# MCU.net
KiCad netlist of a schematic drawn in Altium Designer
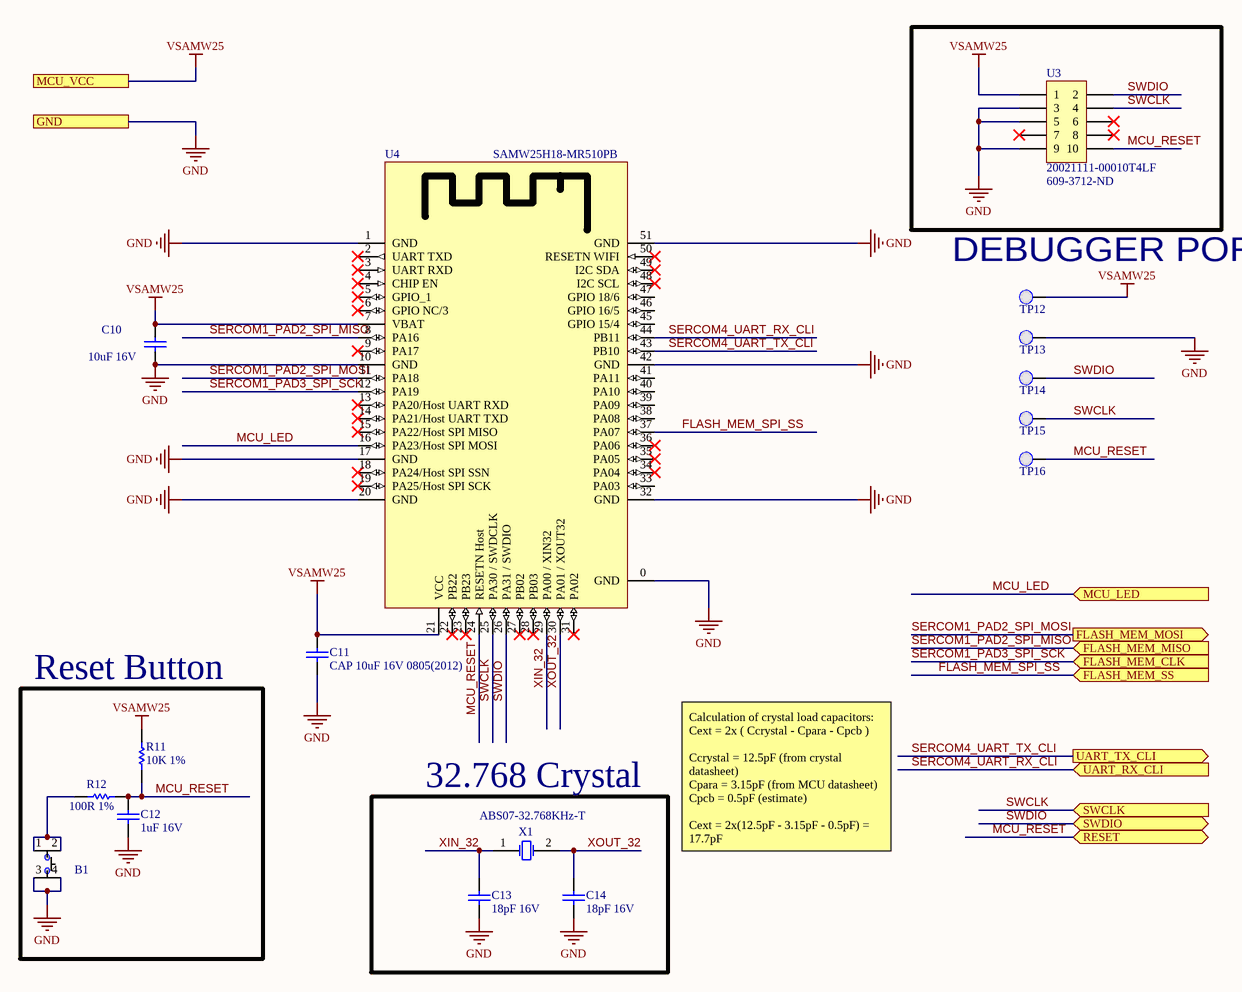
[diagram p0: MCU.SchDoc]

(export (version "E")
  (design (tool "Eeschema 10.0.6"))
  (components
    (comp (ref "B1")
      (value "PTS810 SJK 250 SMTR LFS")
      (footprint "PTS810 SJK 250 SMTR LFS")
      (description "SWITCH TACTILE SPST-NO 0.05A 16V Tactile Switch SPST-NO Top Actuated Surface Mount")
      (fields
        (field (name "MANUFACTURER") "ITT /  C&K Components")
        (field (name "MANUFACTURER PART NUMBER") "PTS810SJK250SMTRLFS")
      )
      (libsource (lib "Schematics") (part "PTS810 SJK 250 SMTR LFS"))
    )
    (comp (ref "C10")
      (value "10uF 16V")
      (footprint "CAPC0805(2012)145_N")
      (description "CAP 10uF 16V ±10% 0805 (2012 Metric) Thickness 1.45mm SMD")
      (fields (field (name "TOLERANCE") "Â±10%"))
      (libsource (lib "Altium Content Vault") (part "CAP"))
    )
    (comp (ref "C11")
      (value "CAP 10uF 16V 0805(2012)")
      (footprint "CAPC0805(2012)145_N")
      (description "CAP 10uF 16V ±10% 0805 (2012 Metric) Thickness 1.45mm SMD")
      (fields (field (name "TOLERANCE") "Â±10%"))
      (libsource (lib "Altium Content Vault") (part "CAP"))
    )
    (comp (ref "C12")
      (value "1uF 16V")
      (footprint "CAPC0603(1608)100_N")
      (description "CAP 1uF 16V ±5% 0603 (1608 Metric) Thickness 1mm SMD")
      (fields (field (name "TOLERANCE") "Â±5%"))
      (libsource (lib "Altium Content Vault") (part "CAP"))
    )
    (comp (ref "C13")
      (value "18pF 16V")
      (footprint "CAPC0603(1608)100_N")
      (description "CAP 18pF 16V ±5% 0603 (1608 Metric) Thickness 1mm SMD")
      (fields (field (name "TOLERANCE") "Â±5%"))
      (libsource (lib "Altium Content Vault") (part "CAP"))
    )
    (comp (ref "C14")
      (value "18pF 16V")
      (footprint "CAPC0603(1608)100_N")
      (description "CAP 18pF 16V ±5% 0603 (1608 Metric) Thickness 1mm SMD")
      (fields (field (name "TOLERANCE") "Â±5%"))
      (libsource (lib "Altium Content Vault") (part "CAP"))
    )
    (comp (ref "R11")
      (value "10K 1%")
      (footprint "RESC0603(1608)_N")
      (description "10K 0.1W 1% 0603 (1608 Metric)  SMD")
      (fields (field (name "POWER") "0.1 W") (field (name "TOLERANCE") "1 %"))
      (libsource (lib "Altium Content Vault") (part "RES"))
    )
    (comp (ref "R12")
      (value "100R 1%")
      (footprint "RESC0603(1608)_N")
      (description "100R 0.1W 1% 0603 (1608 Metric)  SMD")
      (fields (field (name "TOLERANCE") "1 %") (field (name "POWER") "0.1 W"))
      (libsource (lib "Altium Content Vault") (part "RES"))
    )
    (comp (ref "TP12")
      (value "0.1\" Pad")
      (footprint "PCBComponent")
      (libsource (lib "Components - 12.02.20 - 18.05") (part "0.1{dblquote} Pad-A.4"))
    )
    (comp (ref "TP13")
      (value "0.1\" Pad")
      (footprint "PCBComponent")
      (libsource (lib "Components - 12.02.20 - 18.05") (part "0.1{dblquote} Pad-A.4"))
    )
    (comp (ref "TP14")
      (value "0.1\" Pad")
      (footprint "PCBComponent")
      (libsource (lib "Components - 12.02.20 - 18.05") (part "0.1{dblquote} Pad-A.4"))
    )
    (comp (ref "TP15")
      (value "0.1\" Pad")
      (footprint "PCBComponent")
      (libsource (lib "Components - 12.02.20 - 18.05") (part "0.1{dblquote} Pad-A.4"))
    )
    (comp (ref "TP16")
      (value "0.1\" Pad")
      (footprint "PCBComponent")
      (libsource (lib "Components - 12.02.20 - 18.05") (part "0.1{dblquote} Pad-A.4"))
    )
    (comp (ref "U3")
      (value "20021111-00010T4LF")
      (footprint "20021111-00010T4LF")
      (description "CONN HEADER 10POS UNSHD VERT T/H")
      (fields
        (field (name "MANUFACTURER") "Amphenol / FCI")
        (field (name "SUPPLIER PART NUMBER 1") "609-3712-ND")
      )
      (libsource (lib "Schematics") (part "20021111-00010T4LF"))
    )
    (comp (ref "U4")
      (value "SAMW25H18-MR510PB")
      (footprint "SAMW25H18-MR510PB")
      (description "RF TXRX MODULE WIFI TRACE ANT")
      (fields
        (field (name "MANUFACTURER") "Atmel")
        (field (name "MANUFACTURER PART NUMBER") "ATSAMW25H18-MR510PB")
      )
      (libsource (lib "Schematics") (part "SAMW25H18-MR510PB"))
    )
    (comp (ref "X1")
      (value "ABS07-32.768KHz-T")
      (footprint "ABRA-ABS07-2_V")
      (description "Crystal, 32.768 kHz, 12.5 pF, -40 to 85 degC, SMD Low Profile 3.2 x 1.5 x 0.9 mm, Tape and Reel")
      (fields (field (name "MANUFACTURER") "Abracon"))
      (libsource (lib "Altium Content Vault") (part "ABRA-ABS07-2"))
    )
  )
  (nets
    (net (code "1") (name "/FLASH_MEM_SPI_SS") (class "Default")
      (node (ref "U4") (pin "37") (pinfunction "PA07_37") (pintype "bidirectional"))
    )
    (net (code "2") (name "/MCU_LED") (class "Default")
      (node (ref "U4") (pin "16") (pinfunction "PA23/Host_SPI_MOSI_16") (pintype "bidirectional"))
    )
    (net (code "3") (name "/MCU_RESET") (class "Default")
      (node (ref "C12") (pin "2") (pinfunction "2_2") (pintype "passive"))
      (node (ref "R11") (pin "1") (pinfunction "1_1") (pintype "passive"))
      (node (ref "R12") (pin "2") (pinfunction "2_2") (pintype "passive"))
      (node (ref "TP16") (pin "1") (pinfunction "PAD_1") (pintype "passive"))
      (node (ref "U3") (pin "10") (pinfunction "10_10") (pintype "passive"))
      (node (ref "U4") (pin "24") (pinfunction "RESETN_Host_24") (pintype "input"))
    )
    (net (code "4") (name "/SERCOM1_PAD2_SPI_MISO") (class "Default")
      (node (ref "U4") (pin "8") (pinfunction "PA16_8") (pintype "bidirectional"))
    )
    (net (code "5") (name "/SERCOM1_PAD2_SPI_MOSI") (class "Default")
      (node (ref "U4") (pin "11") (pinfunction "PA18_11") (pintype "bidirectional"))
    )
    (net (code "6") (name "/SERCOM1_PAD3_SPI_SCK") (class "Default")
      (node (ref "U4") (pin "12") (pinfunction "PA19_12") (pintype "bidirectional"))
    )
    (net (code "7") (name "/SERCOM4_UART_RX_CLI") (class "Default")
      (node (ref "U4") (pin "44") (pinfunction "PB11_44") (pintype "bidirectional"))
    )
    (net (code "8") (name "/SERCOM4_UART_TX_CLI") (class "Default")
      (node (ref "U4") (pin "43") (pinfunction "PB10_43") (pintype "bidirectional"))
    )
    (net (code "9") (name "/SWCLK") (class "Default")
      (node (ref "TP15") (pin "1") (pinfunction "PAD_1") (pintype "passive"))
      (node (ref "U3") (pin "4") (pinfunction "4_4") (pintype "passive"))
      (node (ref "U4") (pin "25") (pinfunction "PA30_/_SWDCLK_25") (pintype "bidirectional"))
    )
    (net (code "10") (name "/SWDIO") (class "Default")
      (node (ref "TP14") (pin "1") (pinfunction "PAD_1") (pintype "passive"))
      (node (ref "U3") (pin "2") (pinfunction "2_2") (pintype "passive"))
      (node (ref "U4") (pin "26") (pinfunction "PA31_/_SWDIO_26") (pintype "bidirectional"))
    )
    (net (code "11") (name "/XIN_32") (class "Default")
      (node (ref "C13") (pin "2") (pinfunction "2_2") (pintype "passive"))
      (node (ref "U4") (pin "29") (pinfunction "PA00_/_XIN32_29") (pintype "bidirectional"))
      (node (ref "X1") (pin "1") (pinfunction "X1_1") (pintype "passive"))
    )
    (net (code "12") (name "/XOUT_32") (class "Default")
      (node (ref "C14") (pin "2") (pinfunction "2_2") (pintype "passive"))
      (node (ref "U4") (pin "30") (pinfunction "PA01_/_XOUT32_30") (pintype "bidirectional"))
      (node (ref "X1") (pin "2") (pinfunction "X2_2") (pintype "passive"))
    )
    (net (code "13") (name "GND") (class "Default")
      (node (ref "B1") (pin "3") (pinfunction "3_3") (pintype "power_in"))
      (node (ref "B1") (pin "4") (pinfunction "4_4") (pintype "power_in"))
      (node (ref "C10") (pin "1") (pinfunction "1_1") (pintype "passive"))
      (node (ref "C11") (pin "1") (pinfunction "1_1") (pintype "passive"))
      (node (ref "C12") (pin "1") (pinfunction "1_1") (pintype "passive"))
      (node (ref "C13") (pin "1") (pinfunction "1_1") (pintype "passive"))
      (node (ref "C14") (pin "1") (pinfunction "1_1") (pintype "passive"))
      (node (ref "TP13") (pin "1") (pinfunction "PAD_1") (pintype "passive"))
      (node (ref "U3") (pin "3") (pinfunction "3_3") (pintype "passive"))
      (node (ref "U3") (pin "5") (pinfunction "5_5") (pintype "passive"))
      (node (ref "U3") (pin "9") (pinfunction "9_9") (pintype "passive"))
      (node (ref "U4") (pin "0") (pinfunction "GND_0") (pintype "power_in"))
      (node (ref "U4") (pin "1") (pinfunction "GND_1") (pintype "power_in"))
      (node (ref "U4") (pin "10") (pinfunction "GND_10") (pintype "power_in"))
      (node (ref "U4") (pin "17") (pinfunction "GND_17") (pintype "power_in"))
      (node (ref "U4") (pin "20") (pinfunction "GND_20") (pintype "power_in"))
      (node (ref "U4") (pin "32") (pinfunction "GND_32") (pintype "power_in"))
      (node (ref "U4") (pin "42") (pinfunction "GND_42") (pintype "power_in"))
      (node (ref "U4") (pin "51") (pinfunction "GND_51") (pintype "power_in"))
    )
    (net (code "14") (name "Net-(B1-Pad1)") (class "Default")
      (node (ref "B1") (pin "1") (pinfunction "1_1") (pintype "power_in"))
      (node (ref "B1") (pin "2") (pinfunction "2_2") (pintype "power_in"))
      (node (ref "R12") (pin "1") (pinfunction "1_1") (pintype "passive"))
    )
    (net (code "15") (name "VSAMW25") (class "Default")
      (node (ref "C10") (pin "2") (pinfunction "2_2") (pintype "passive"))
      (node (ref "C11") (pin "2") (pinfunction "2_2") (pintype "passive"))
      (node (ref "R11") (pin "2") (pinfunction "2_2") (pintype "passive"))
      (node (ref "TP12") (pin "1") (pinfunction "PAD_1") (pintype "passive"))
      (node (ref "U3") (pin "1") (pinfunction "1_1") (pintype "passive"))
      (node (ref "U4") (pin "21") (pinfunction "VCC_21") (pintype "power_in"))
      (node (ref "U4") (pin "7") (pinfunction "VBAT_7") (pintype "power_in"))
    )
    (net (code "16") (name "unconnected-(U3-Pad6)") (class "Default")
      (node (ref "U3") (pin "6") (pinfunction "6_6") (pintype "passive+no_connect"))
    )
    (net (code "17") (name "unconnected-(U3-Pad7)") (class "Default")
      (node (ref "U3") (pin "7") (pinfunction "7_7") (pintype "passive+no_connect"))
    )
    (net (code "18") (name "unconnected-(U3-Pad8)") (class "Default")
      (node (ref "U3") (pin "8") (pinfunction "8_8") (pintype "passive+no_connect"))
    )
    (net (code "19") (name "unconnected-(U4-CHIP_EN-Pad4)") (class "Default")
      (node (ref "U4") (pin "4") (pinfunction "CHIP_EN_4") (pintype "input+no_connect"))
    )
    (net (code "20") (name "unconnected-(U4-GPIO_1-Pad5)") (class "Default")
      (node (ref "U4") (pin "5") (pinfunction "GPIO_1_5") (pintype "bidirectional+no_connect"))
    )
    (net (code "21") (name "unconnected-(U4-GPIO_15{slash}4-Pad45)") (class "Default")
      (node (ref "U4") (pin "45") (pinfunction "GPIO_15/4_45") (pintype "bidirectional"))
    )
    (net (code "22") (name "unconnected-(U4-GPIO_16{slash}5-Pad46)") (class "Default")
      (node (ref "U4") (pin "46") (pinfunction "GPIO_16/5_46") (pintype "bidirectional"))
    )
    (net (code "23") (name "unconnected-(U4-GPIO_18{slash}6-Pad47)") (class "Default")
      (node (ref "U4") (pin "47") (pinfunction "GPIO_18/6_47") (pintype "bidirectional"))
    )
    (net (code "24") (name "unconnected-(U4-GPIO_NC{slash}3-Pad6)") (class "Default")
      (node (ref "U4") (pin "6") (pinfunction "GPIO_NC/3_6") (pintype "bidirectional+no_connect"))
    )
    (net (code "25") (name "unconnected-(U4-I2C_SCL-Pad48)") (class "Default")
      (node (ref "U4") (pin "48") (pinfunction "I2C_SCL_48") (pintype "bidirectional+no_connect"))
    )
    (net (code "26") (name "unconnected-(U4-I2C_SDA-Pad49)") (class "Default")
      (node (ref "U4") (pin "49") (pinfunction "I2C_SDA_49") (pintype "bidirectional+no_connect"))
    )
    (net (code "27") (name "unconnected-(U4-PA02-Pad31)") (class "Default")
      (node (ref "U4") (pin "31") (pinfunction "PA02_31") (pintype "bidirectional+no_connect"))
    )
    (net (code "28") (name "unconnected-(U4-PA03-Pad33)") (class "Default")
      (node (ref "U4") (pin "33") (pinfunction "PA03_33") (pintype "bidirectional"))
    )
    (net (code "29") (name "unconnected-(U4-PA04-Pad34)") (class "Default")
      (node (ref "U4") (pin "34") (pinfunction "PA04_34") (pintype "bidirectional+no_connect"))
    )
    (net (code "30") (name "unconnected-(U4-PA05-Pad35)") (class "Default")
      (node (ref "U4") (pin "35") (pinfunction "PA05_35") (pintype "bidirectional+no_connect"))
    )
    (net (code "31") (name "unconnected-(U4-PA06-Pad36)") (class "Default")
      (node (ref "U4") (pin "36") (pinfunction "PA06_36") (pintype "bidirectional+no_connect"))
    )
    (net (code "32") (name "unconnected-(U4-PA08-Pad38)") (class "Default")
      (node (ref "U4") (pin "38") (pinfunction "PA08_38") (pintype "bidirectional"))
    )
    (net (code "33") (name "unconnected-(U4-PA09-Pad39)") (class "Default")
      (node (ref "U4") (pin "39") (pinfunction "PA09_39") (pintype "bidirectional"))
    )
    (net (code "34") (name "unconnected-(U4-PA10-Pad40)") (class "Default")
      (node (ref "U4") (pin "40") (pinfunction "PA10_40") (pintype "bidirectional"))
    )
    (net (code "35") (name "unconnected-(U4-PA11-Pad41)") (class "Default")
      (node (ref "U4") (pin "41") (pinfunction "PA11_41") (pintype "bidirectional"))
    )
    (net (code "36") (name "unconnected-(U4-PA17-Pad9)") (class "Default")
      (node (ref "U4") (pin "9") (pinfunction "PA17_9") (pintype "bidirectional+no_connect"))
    )
    (net (code "37") (name "unconnected-(U4-PA20{slash}Host_UART_RXD-Pad13)") (class "Default")
      (node (ref "U4") (pin "13") (pinfunction "PA20/Host_UART_RXD_13") (pintype "bidirectional+no_connect"))
    )
    (net (code "38") (name "unconnected-(U4-PA21{slash}Host_UART_TXD-Pad14)") (class "Default")
      (node (ref "U4") (pin "14") (pinfunction "PA21/Host_UART_TXD_14") (pintype "bidirectional+no_connect"))
    )
    (net (code "39") (name "unconnected-(U4-PA22{slash}Host_SPI_MISO-Pad15)") (class "Default")
      (node (ref "U4") (pin "15") (pinfunction "PA22/Host_SPI_MISO_15") (pintype "bidirectional+no_connect"))
    )
    (net (code "40") (name "unconnected-(U4-PA24{slash}Host_SPI_SSN-Pad18)") (class "Default")
      (node (ref "U4") (pin "18") (pinfunction "PA24/Host_SPI_SSN_18") (pintype "bidirectional+no_connect"))
    )
    (net (code "41") (name "unconnected-(U4-PA25{slash}Host_SPI_SCK-Pad19)") (class "Default")
      (node (ref "U4") (pin "19") (pinfunction "PA25/Host_SPI_SCK_19") (pintype "bidirectional+no_connect"))
    )
    (net (code "42") (name "unconnected-(U4-PB02-Pad27)") (class "Default")
      (node (ref "U4") (pin "27") (pinfunction "PB02_27") (pintype "bidirectional+no_connect"))
    )
    (net (code "43") (name "unconnected-(U4-PB03-Pad28)") (class "Default")
      (node (ref "U4") (pin "28") (pinfunction "PB03_28") (pintype "bidirectional+no_connect"))
    )
    (net (code "44") (name "unconnected-(U4-PB22-Pad22)") (class "Default")
      (node (ref "U4") (pin "22") (pinfunction "PB22_22") (pintype "bidirectional+no_connect"))
    )
    (net (code "45") (name "unconnected-(U4-PB23-Pad23)") (class "Default")
      (node (ref "U4") (pin "23") (pinfunction "PB23_23") (pintype "bidirectional+no_connect"))
    )
    (net (code "46") (name "unconnected-(U4-RESETN_WIFI-Pad50)") (class "Default")
      (node (ref "U4") (pin "50") (pinfunction "RESETN_WIFI_50") (pintype "input+no_connect"))
    )
    (net (code "47") (name "unconnected-(U4-UART_RXD-Pad3)") (class "Default")
      (node (ref "U4") (pin "3") (pinfunction "UART_RXD_3") (pintype "input+no_connect"))
    )
    (net (code "48") (name "unconnected-(U4-UART_TXD-Pad2)") (class "Default")
      (node (ref "U4") (pin "2") (pinfunction "UART_TXD_2") (pintype "output+no_connect"))
    )
  )
)
